# battery_monitor.net
KiCad netlist of a schematic drawn in EAGLE
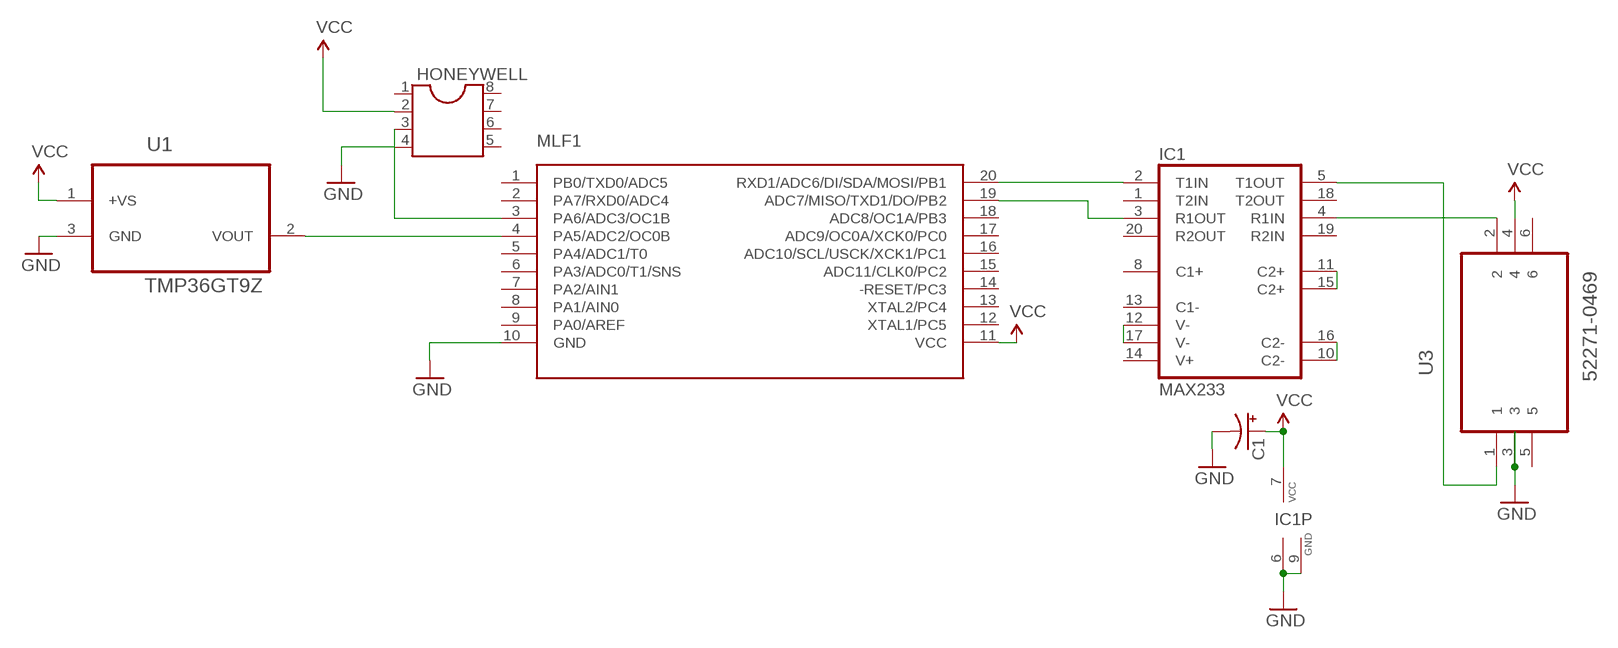
[diagram p0: schematic, sheet 1]

(export (version "E")
  (design (tool "Eeschema 10.0.6"))
  (components
    (comp (ref "C1")
      (value "CAP_POLPTH1")
      (footprint "eagle-import:CPOL-RADIAL-100UF-25V")
      (libsource (lib "eagle-import") (part "CAP_POLPTH1"))
    )
    (comp (ref "HONEYWELL")
      (value "DIL8S")
      (footprint "eagle-import:SOCKET-08")
      (libsource (lib "eagle-import") (part "DIL8S"))
    )
    (comp (ref "IC1")
      (value "MAX233")
      (footprint "eagle-import:DIL20")
      (fields (field (name "MPN") "MAX233ACPP+G36"))
      (libsource (lib "eagle-import") (part "MAX233"))
    )
    (comp (ref "MLF1")
      (value "ATTINY1634SOIC20")
      (footprint "eagle-import:SOIC20")
      (libsource (lib "eagle-import") (part "ATTINY1634SOIC20"))
    )
    (comp (ref "U1")
      (value "TMP36GT9Z")
      (footprint "eagle-import:TO127P254X533-3P")
      (libsource (lib "eagle-import") (part "TMP36GT9Z"))
    )
    (comp (ref "U3")
      (value "52271-0469")
      (footprint "eagle-import:MOLEX_52271-0469")
      (libsource (lib "eagle-import") (part "52271-0469"))
    )
  )
  (nets
    (net (code "1") (name "GND") (class "Default")
      (node (ref "C1") (pin "2") (pinfunction "-_2") (pintype "passive"))
      (node (ref "HONEYWELL") (pin "4") (pinfunction "4_4") (pintype "passive"))
      (node (ref "IC1") (pin "6") (pinfunction "GND_6") (pintype "power_in"))
      (node (ref "IC1") (pin "9") (pinfunction "GND_9") (pintype "power_in"))
      (node (ref "MLF1") (pin "10") (pinfunction "GND_10") (pintype "power_in"))
      (node (ref "U1") (pin "3") (pinfunction "GND_3") (pintype "passive"))
      (node (ref "U3") (pin "3") (pinfunction "3_3") (pintype "passive"))
    )
    (net (code "2") (name "Net-(IC1A-C2+-Pad11)") (class "Default")
      (node (ref "IC1") (pin "11") (pinfunction "C2+_11") (pintype "bidirectional"))
      (node (ref "IC1") (pin "15") (pinfunction "C2+_15") (pintype "bidirectional"))
    )
    (net (code "3") (name "Net-(IC1A-C2--Pad10)") (class "Default")
      (node (ref "IC1") (pin "10") (pinfunction "C2-_10") (pintype "bidirectional"))
      (node (ref "IC1") (pin "16") (pinfunction "C2-_16") (pintype "bidirectional"))
    )
    (net (code "4") (name "Net-(IC1A-R1IN)") (class "Default")
      (node (ref "IC1") (pin "4") (pinfunction "R1IN_4") (pintype "input"))
      (node (ref "U3") (pin "2") (pinfunction "2_2") (pintype "passive"))
    )
    (net (code "5") (name "Net-(IC1A-R1OUT)") (class "Default")
      (node (ref "IC1") (pin "3") (pinfunction "R1OUT_3") (pintype "output"))
      (node (ref "MLF1") (pin "19") (pinfunction "ADC7/MISO/TXD1/DO/PB2_19") (pintype "bidirectional"))
    )
    (net (code "6") (name "Net-(IC1A-T1IN)") (class "Default")
      (node (ref "IC1") (pin "2") (pinfunction "T1IN_2") (pintype "input"))
      (node (ref "MLF1") (pin "20") (pinfunction "RXD1/ADC6/DI/SDA/MOSI/PB1_20") (pintype "bidirectional"))
    )
    (net (code "7") (name "Net-(IC1A-T1OUT)") (class "Default")
      (node (ref "IC1") (pin "5") (pinfunction "T1OUT_5") (pintype "output"))
      (node (ref "U3") (pin "1") (pinfunction "1_1") (pintype "passive"))
    )
    (net (code "8") (name "Net-(IC1A-V--Pad12)") (class "Default")
      (node (ref "IC1") (pin "12") (pinfunction "V-_12") (pintype "bidirectional"))
      (node (ref "IC1") (pin "17") (pinfunction "V-_17") (pintype "bidirectional"))
    )
    (net (code "9") (name "Net-(MLF1-PA5{slash}ADC2{slash}OC0B)") (class "Default")
      (node (ref "MLF1") (pin "4") (pinfunction "PA5/ADC2/OC0B_4") (pintype "bidirectional"))
      (node (ref "U1") (pin "2") (pinfunction "VOUT_2") (pintype "passive"))
    )
    (net (code "10") (name "Net-(MLF1-PA6{slash}ADC3{slash}OC1B)") (class "Default")
      (node (ref "HONEYWELL") (pin "3") (pinfunction "3_3") (pintype "passive"))
      (node (ref "MLF1") (pin "3") (pinfunction "PA6/ADC3/OC1B_3") (pintype "bidirectional"))
    )
    (net (code "11") (name "VCC") (class "Default")
      (node (ref "C1") (pin "1") (pinfunction "+_1") (pintype "passive"))
      (node (ref "HONEYWELL") (pin "2") (pinfunction "2_2") (pintype "passive"))
      (node (ref "IC1") (pin "7") (pinfunction "VCC_7") (pintype "power_in"))
      (node (ref "MLF1") (pin "11") (pinfunction "VCC_11") (pintype "power_in"))
      (node (ref "U1") (pin "1") (pinfunction "+VS_1") (pintype "power_in"))
      (node (ref "U3") (pin "4") (pinfunction "4_4") (pintype "passive"))
    )
    (net (code "12") (name "unconnected-(HONEYWELL-Pad1)") (class "Default")
      (node (ref "HONEYWELL") (pin "1") (pinfunction "1_1") (pintype "passive"))
    )
    (net (code "13") (name "unconnected-(HONEYWELL-Pad5)") (class "Default")
      (node (ref "HONEYWELL") (pin "5") (pinfunction "5_5") (pintype "passive"))
    )
    (net (code "14") (name "unconnected-(HONEYWELL-Pad6)") (class "Default")
      (node (ref "HONEYWELL") (pin "6") (pinfunction "6_6") (pintype "passive"))
    )
    (net (code "15") (name "unconnected-(HONEYWELL-Pad7)") (class "Default")
      (node (ref "HONEYWELL") (pin "7") (pinfunction "7_7") (pintype "passive"))
    )
    (net (code "16") (name "unconnected-(HONEYWELL-Pad8)") (class "Default")
      (node (ref "HONEYWELL") (pin "8") (pinfunction "8_8") (pintype "passive"))
    )
    (net (code "17") (name "unconnected-(IC1A-C1+-Pad8)") (class "Default")
      (node (ref "IC1") (pin "8") (pinfunction "C1+_8") (pintype "bidirectional"))
    )
    (net (code "18") (name "unconnected-(IC1A-C1--Pad13)") (class "Default")
      (node (ref "IC1") (pin "13") (pinfunction "C1-_13") (pintype "bidirectional"))
    )
    (net (code "19") (name "unconnected-(IC1A-R2IN-Pad19)") (class "Default")
      (node (ref "IC1") (pin "19") (pinfunction "R2IN_19") (pintype "input"))
    )
    (net (code "20") (name "unconnected-(IC1A-R2OUT-Pad20)") (class "Default")
      (node (ref "IC1") (pin "20") (pinfunction "R2OUT_20") (pintype "output"))
    )
    (net (code "21") (name "unconnected-(IC1A-T2IN-Pad1)") (class "Default")
      (node (ref "IC1") (pin "1") (pinfunction "T2IN_1") (pintype "input"))
    )
    (net (code "22") (name "unconnected-(IC1A-T2OUT-Pad18)") (class "Default")
      (node (ref "IC1") (pin "18") (pinfunction "T2OUT_18") (pintype "output"))
    )
    (net (code "23") (name "unconnected-(IC1A-V+-Pad14)") (class "Default")
      (node (ref "IC1") (pin "14") (pinfunction "V+_14") (pintype "bidirectional"))
    )
    (net (code "24") (name "unconnected-(MLF1--RESET{slash}PC3-Pad14)") (class "Default")
      (node (ref "MLF1") (pin "14") (pinfunction "-RESET/PC3_14") (pintype "bidirectional"))
    )
    (net (code "25") (name "unconnected-(MLF1-ADC8{slash}OC1A{slash}PB3-Pad18)") (class "Default")
      (node (ref "MLF1") (pin "18") (pinfunction "ADC8/OC1A/PB3_18") (pintype "bidirectional"))
    )
    (net (code "26") (name "unconnected-(MLF1-ADC9{slash}OC0A{slash}XCK0{slash}PC0-Pad17)") (class "Default")
      (node (ref "MLF1") (pin "17") (pinfunction "ADC9/OC0A/XCK0/PC0_17") (pintype "bidirectional"))
    )
    (net (code "27") (name "unconnected-(MLF1-ADC10{slash}SCL{slash}USCK{slash}XCK1{slash}PC1-Pad16)") (class "Default")
      (node (ref "MLF1") (pin "16") (pinfunction "ADC10/SCL/USCK/XCK1/PC1_16") (pintype "bidirectional"))
    )
    (net (code "28") (name "unconnected-(MLF1-ADC11{slash}CLK0{slash}PC2-Pad15)") (class "Default")
      (node (ref "MLF1") (pin "15") (pinfunction "ADC11/CLK0/PC2_15") (pintype "bidirectional"))
    )
    (net (code "29") (name "unconnected-(MLF1-PA0{slash}AREF-Pad9)") (class "Default")
      (node (ref "MLF1") (pin "9") (pinfunction "PA0/AREF_9") (pintype "bidirectional"))
    )
    (net (code "30") (name "unconnected-(MLF1-PA1{slash}AIN0-Pad8)") (class "Default")
      (node (ref "MLF1") (pin "8") (pinfunction "PA1/AIN0_8") (pintype "bidirectional"))
    )
    (net (code "31") (name "unconnected-(MLF1-PA2{slash}AIN1-Pad7)") (class "Default")
      (node (ref "MLF1") (pin "7") (pinfunction "PA2/AIN1_7") (pintype "bidirectional"))
    )
    (net (code "32") (name "unconnected-(MLF1-PA3{slash}ADC0{slash}T1{slash}SNS-Pad6)") (class "Default")
      (node (ref "MLF1") (pin "6") (pinfunction "PA3/ADC0/T1/SNS_6") (pintype "bidirectional"))
    )
    (net (code "33") (name "unconnected-(MLF1-PA4{slash}ADC1{slash}T0-Pad5)") (class "Default")
      (node (ref "MLF1") (pin "5") (pinfunction "PA4/ADC1/T0_5") (pintype "bidirectional"))
    )
    (net (code "34") (name "unconnected-(MLF1-PA7{slash}RXD0{slash}ADC4-Pad2)") (class "Default")
      (node (ref "MLF1") (pin "2") (pinfunction "PA7/RXD0/ADC4_2") (pintype "bidirectional"))
    )
    (net (code "35") (name "unconnected-(MLF1-PB0{slash}TXD0{slash}ADC5-Pad1)") (class "Default")
      (node (ref "MLF1") (pin "1") (pinfunction "PB0/TXD0/ADC5_1") (pintype "bidirectional"))
    )
    (net (code "36") (name "unconnected-(MLF1-XTAL1{slash}PC5-Pad12)") (class "Default")
      (node (ref "MLF1") (pin "12") (pinfunction "XTAL1/PC5_12") (pintype "bidirectional"))
    )
    (net (code "37") (name "unconnected-(MLF1-XTAL2{slash}PC4-Pad13)") (class "Default")
      (node (ref "MLF1") (pin "13") (pinfunction "XTAL2/PC4_13") (pintype "bidirectional"))
    )
    (net (code "38") (name "unconnected-(U3-Pad5)") (class "Default")
      (node (ref "U3") (pin "5") (pinfunction "5_5") (pintype "passive"))
    )
    (net (code "39") (name "unconnected-(U3-Pad6)") (class "Default")
      (node (ref "U3") (pin "6") (pinfunction "6_6") (pintype "passive"))
    )
  )
)
